# circuit.net
KiCad netlist of a schematic drawn in EAGLE
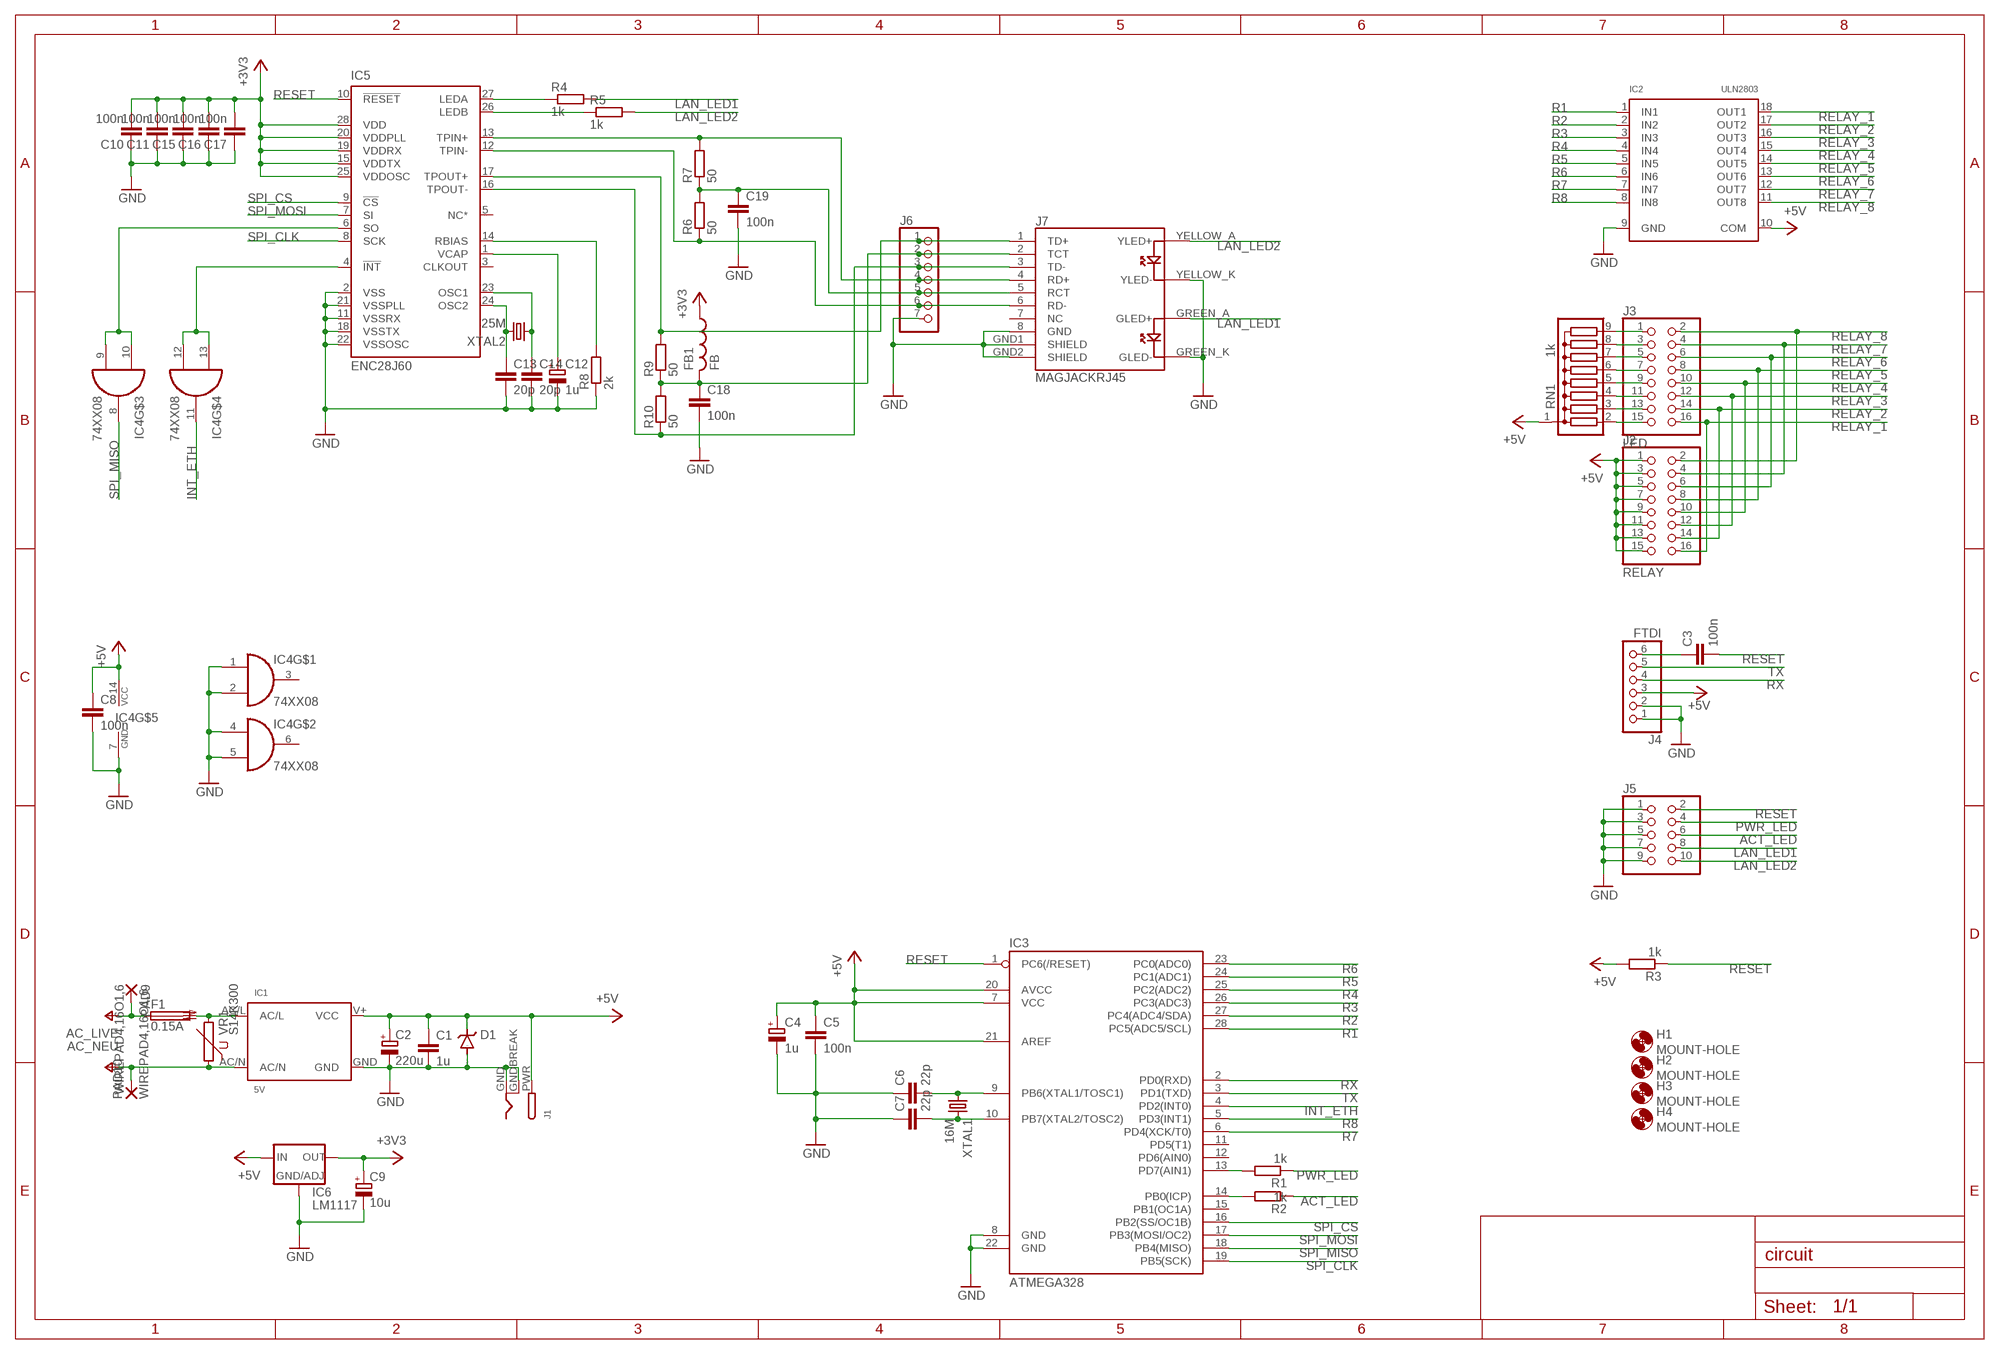
[diagram p0: schematic, sheet 1]

(export (version "E")
  (design (tool "Eeschema 10.0.6"))
  (components
    (comp (ref "C1")
      (value "1u")
      (footprint "eagle-import:C050-025X075")
      (libsource (lib "eagle-import") (part "CAPACITORC050-025X075"))
    )
    (comp (ref "C2")
      (value "220u")
      (footprint "eagle-import:E2,5-6")
      (libsource (lib "eagle-import") (part "CAPACITOR_POL2.5/6"))
    )
    (comp (ref "C3")
      (value "100n")
      (footprint "eagle-import:C050-025X075")
      (libsource (lib "eagle-import") (part "CAPACITORC050-025X075"))
    )
    (comp (ref "C4")
      (value "1u")
      (footprint "eagle-import:E5-5")
      (libsource (lib "eagle-import") (part "CAPACITOR_POL5/5"))
    )
    (comp (ref "C5")
      (value "100n")
      (footprint "eagle-import:C050-025X075")
      (libsource (lib "eagle-import") (part "CAPACITORC050-025X075"))
    )
    (comp (ref "C6")
      (value "22p")
      (footprint "eagle-import:C025-025X050")
      (libsource (lib "eagle-import") (part "CAPACITORC025-025X050"))
    )
    (comp (ref "C7")
      (value "22p")
      (footprint "eagle-import:C025-025X050")
      (libsource (lib "eagle-import") (part "CAPACITORC025-025X050"))
    )
    (comp (ref "C8")
      (value "100n")
      (footprint "eagle-import:C050-025X075")
      (libsource (lib "eagle-import") (part "CAPACITORC050-025X075"))
    )
    (comp (ref "C9")
      (value "10u")
      (footprint "eagle-import:E5-5")
      (libsource (lib "eagle-import") (part "CAPACITOR_POL5/5"))
    )
    (comp (ref "C10")
      (value "100n")
      (footprint "eagle-import:C050-025X075")
      (libsource (lib "eagle-import") (part "CAPACITORC050-025X075"))
    )
    (comp (ref "C11")
      (value "100n")
      (footprint "eagle-import:C050-025X075")
      (libsource (lib "eagle-import") (part "CAPACITORC050-025X075"))
    )
    (comp (ref "C12")
      (value "1u")
      (footprint "eagle-import:E5-5")
      (libsource (lib "eagle-import") (part "CAPACITOR_POL5/5"))
    )
    (comp (ref "C13")
      (value "20p")
      (footprint "eagle-import:C025-025X050")
      (libsource (lib "eagle-import") (part "CAPACITORC025-025X050"))
    )
    (comp (ref "C14")
      (value "20p")
      (footprint "eagle-import:C025-025X050")
      (libsource (lib "eagle-import") (part "CAPACITORC025-025X050"))
    )
    (comp (ref "C15")
      (value "100n")
      (footprint "eagle-import:C050-025X075")
      (libsource (lib "eagle-import") (part "CAPACITORC050-025X075"))
    )
    (comp (ref "C16")
      (value "100n")
      (footprint "eagle-import:C050-025X075")
      (libsource (lib "eagle-import") (part "CAPACITORC050-025X075"))
    )
    (comp (ref "C17")
      (value "100n")
      (footprint "eagle-import:C050-025X075")
      (libsource (lib "eagle-import") (part "CAPACITORC050-025X075"))
    )
    (comp (ref "C18")
      (value "100n")
      (footprint "eagle-import:C050-025X075")
      (libsource (lib "eagle-import") (part "CAPACITORC050-025X075"))
    )
    (comp (ref "C19")
      (value "100n")
      (footprint "eagle-import:C050-025X075")
      (libsource (lib "eagle-import") (part "CAPACITORC050-025X075"))
    )
    (comp (ref "D1")
      (value "DIODE-TVSDO15")
      (footprint "eagle-import:DO15")
      (libsource (lib "eagle-import") (part "DIODE-TVSDO15"))
    )
    (comp (ref "F1")
      (value "0.15A")
      (footprint "eagle-import:5X20_FUSE")
      (libsource (lib "eagle-import") (part "5X20_FUSE"))
    )
    (comp (ref "FB1") (value "FB") (footprint "eagle-import:FB") (libsource (lib "eagle-import") (part "FB")))
    (comp (ref "H1")
      (value "MOUNT-HOLE")
      (footprint "eagle-import:3,2")
      (libsource (lib "eagle-import") (part "MOUNT-HOLE"))
    )
    (comp (ref "H2")
      (value "MOUNT-HOLE")
      (footprint "eagle-import:3,2")
      (libsource (lib "eagle-import") (part "MOUNT-HOLE"))
    )
    (comp (ref "H3")
      (value "MOUNT-HOLE")
      (footprint "eagle-import:3,2")
      (libsource (lib "eagle-import") (part "MOUNT-HOLE"))
    )
    (comp (ref "H4")
      (value "MOUNT-HOLE")
      (footprint "eagle-import:3,2")
      (libsource (lib "eagle-import") (part "MOUNT-HOLE"))
    )
    (comp (ref "IC1")
      (value "5V")
      (footprint "eagle-import:LD_AMEL10")
      (libsource (lib "eagle-import") (part "AC-DC_PSUAMEL10"))
    )
    (comp (ref "IC2")
      (value "ULN2803")
      (footprint "eagle-import:DIL18")
      (libsource (lib "eagle-import") (part "ULN2803"))
    )
    (comp (ref "IC3")
      (value "ATMEGA328")
      (footprint "eagle-import:DIL28")
      (libsource (lib "eagle-import") (part "ATMEGA328"))
    )
    (comp (ref "IC4")
      (value "74XX08")
      (footprint "eagle-import:DIL14")
      (libsource (lib "eagle-import") (part "74XX08"))
    )
    (comp (ref "IC5")
      (value "ENC28J60")
      (footprint "eagle-import:DIL28")
      (libsource (lib "eagle-import") (part "ENC28J60"))
    )
    (comp (ref "IC6")
      (value "LM1117")
      (footprint "eagle-import:TO220V")
      (libsource (lib "eagle-import") (part "LM1117"))
    )
    (comp (ref "J1")
      (value "DCBARRELPTH")
      (footprint "eagle-import:DCJACK_2MM_PTH")
      (libsource (lib "eagle-import") (part "DCBARRELPTH"))
    )
    (comp (ref "J2")
      (value "RELAY")
      (footprint "eagle-import:2X08")
      (libsource (lib "eagle-import") (part "PINHD-2X8"))
    )
    (comp (ref "J3")
      (value "LED")
      (footprint "eagle-import:2X08")
      (libsource (lib "eagle-import") (part "PINHD-2X8"))
    )
    (comp (ref "J4")
      (value "FTDI")
      (footprint "eagle-import:1X06")
      (libsource (lib "eagle-import") (part "PINHD-1X6"))
    )
    (comp (ref "J5")
      (value "PINHD-2X5")
      (footprint "eagle-import:2X05")
      (libsource (lib "eagle-import") (part "PINHD-2X5"))
    )
    (comp (ref "J6")
      (value "PINHD-1X7")
      (footprint "eagle-import:1X07")
      (libsource (lib "eagle-import") (part "PINHD-1X7"))
    )
    (comp (ref "J7")
      (value "MAGJACKRJ45")
      (footprint "eagle-import:MAGJACK")
      (libsource (lib "eagle-import") (part "MAGJACKRJ45"))
    )
    (comp (ref "PAD9")
      (value "WIREPAD4,16O1,6")
      (footprint "eagle-import:4,16O1,6")
      (libsource (lib "eagle-import") (part "WIREPAD4,16O1,6"))
    )
    (comp (ref "PAD10")
      (value "WIREPAD4,16O1,6")
      (footprint "eagle-import:4,16O1,6")
      (libsource (lib "eagle-import") (part "WIREPAD4,16O1,6"))
    )
    (comp (ref "R1")
      (value "1k")
      (footprint "eagle-import:0207_10")
      (libsource (lib "eagle-import") (part "RESISTOR"))
    )
    (comp (ref "R2")
      (value "1k")
      (footprint "eagle-import:0207_10")
      (libsource (lib "eagle-import") (part "RESISTOR"))
    )
    (comp (ref "R3")
      (value "1k")
      (footprint "eagle-import:0207_10")
      (libsource (lib "eagle-import") (part "RESISTOR"))
    )
    (comp (ref "R4")
      (value "1k")
      (footprint "eagle-import:0207_10")
      (libsource (lib "eagle-import") (part "RESISTOR"))
    )
    (comp (ref "R5")
      (value "1k")
      (footprint "eagle-import:0207_10")
      (libsource (lib "eagle-import") (part "RESISTOR"))
    )
    (comp (ref "R6")
      (value "50")
      (footprint "eagle-import:0207_10")
      (libsource (lib "eagle-import") (part "RESISTOR"))
    )
    (comp (ref "R7")
      (value "50")
      (footprint "eagle-import:0207_10")
      (libsource (lib "eagle-import") (part "RESISTOR"))
    )
    (comp (ref "R8")
      (value "2k")
      (footprint "eagle-import:0207_10")
      (libsource (lib "eagle-import") (part "RESISTOR"))
    )
    (comp (ref "R9")
      (value "50")
      (footprint "eagle-import:0207_10")
      (libsource (lib "eagle-import") (part "RESISTOR"))
    )
    (comp (ref "R10")
      (value "50")
      (footprint "eagle-import:0207_10")
      (libsource (lib "eagle-import") (part "RESISTOR"))
    )
    (comp (ref "RN1")
      (value "1k")
      (footprint "eagle-import:SIL9")
      (libsource (lib "eagle-import") (part "G08R"))
    )
    (comp (ref "VR1")
      (value "S14K300")
      (footprint "eagle-import:S14K300")
      (libsource (lib "eagle-import") (part "S14K300"))
    )
    (comp (ref "XTAL1")
      (value "16M")
      (footprint "eagle-import:HC49_S")
      (libsource (lib "eagle-import") (part "CRYSTAL"))
    )
    (comp (ref "XTAL2")
      (value "25M")
      (footprint "eagle-import:HC49_S")
      (libsource (lib "eagle-import") (part "CRYSTAL"))
    )
  )
  (nets
    (net (code "1") (name "+3V3") (class "Default")
      (node (ref "C10") (pin "2") (pinfunction "2_2") (pintype "passive"))
      (node (ref "C11") (pin "2") (pinfunction "2_2") (pintype "passive"))
      (node (ref "C15") (pin "2") (pinfunction "2_2") (pintype "passive"))
      (node (ref "C16") (pin "2") (pinfunction "2_2") (pintype "passive"))
      (node (ref "C17") (pin "2") (pinfunction "2_2") (pintype "passive"))
      (node (ref "C9") (pin "+") (pinfunction "+_+") (pintype "passive"))
      (node (ref "FB1") (pin "P$1") (pinfunction "1_P$1") (pintype "passive"))
      (node (ref "IC5") (pin "15") (pinfunction "VDDTX_15") (pintype "input"))
      (node (ref "IC5") (pin "19") (pinfunction "VDDRX_19") (pintype "input"))
      (node (ref "IC5") (pin "20") (pinfunction "VDDPLL_20") (pintype "input"))
      (node (ref "IC5") (pin "25") (pinfunction "VDDOSC_25") (pintype "input"))
      (node (ref "IC5") (pin "28") (pinfunction "VDD_28") (pintype "input"))
      (node (ref "IC6") (pin "2") (pinfunction "OUT_2") (pintype "passive"))
    )
    (net (code "2") (name "+5V") (class "Default")
      (node (ref "C1") (pin "1") (pinfunction "1_1") (pintype "passive"))
      (node (ref "C2") (pin "+") (pinfunction "+_+") (pintype "passive"))
      (node (ref "C4") (pin "+") (pinfunction "+_+") (pintype "passive"))
      (node (ref "C5") (pin "1") (pinfunction "1_1") (pintype "passive"))
      (node (ref "C8") (pin "1") (pinfunction "1_1") (pintype "passive"))
      (node (ref "D1") (pin "C") (pinfunction "C_C") (pintype "passive"))
      (node (ref "IC1") (pin "V+") (pinfunction "VCC_V+") (pintype "bidirectional"))
      (node (ref "IC2") (pin "10") (pinfunction "COM_10") (pintype "bidirectional"))
      (node (ref "IC3") (pin "20") (pinfunction "AVCC_20") (pintype "bidirectional"))
      (node (ref "IC3") (pin "21") (pinfunction "AREF_21") (pintype "bidirectional"))
      (node (ref "IC3") (pin "7") (pinfunction "VCC_7") (pintype "bidirectional"))
      (node (ref "IC4") (pin "14") (pinfunction "VCC_14") (pintype "power_in"))
      (node (ref "IC6") (pin "3") (pinfunction "IN_3") (pintype "input"))
      (node (ref "J1") (pin "PWR") (pinfunction "PWR_PWR") (pintype "power_in"))
      (node (ref "J2") (pin "1") (pinfunction "1_1") (pintype "passive"))
      (node (ref "J2") (pin "11") (pinfunction "11_11") (pintype "passive"))
      (node (ref "J2") (pin "13") (pinfunction "13_13") (pintype "passive"))
      (node (ref "J2") (pin "15") (pinfunction "15_15") (pintype "passive"))
      (node (ref "J2") (pin "3") (pinfunction "3_3") (pintype "passive"))
      (node (ref "J2") (pin "5") (pinfunction "5_5") (pintype "passive"))
      (node (ref "J2") (pin "7") (pinfunction "7_7") (pintype "passive"))
      (node (ref "J2") (pin "9") (pinfunction "9_9") (pintype "passive"))
      (node (ref "J4") (pin "3") (pinfunction "3_3") (pintype "passive"))
      (node (ref "R3") (pin "2") (pinfunction "2_2") (pintype "passive"))
      (node (ref "RN1") (pin "1") (pinfunction "1_1") (pintype "passive"))
    )
    (net (code "3") (name "/ACT_LED") (class "Default")
      (node (ref "J5") (pin "6") (pinfunction "6_6") (pintype "passive"))
      (node (ref "R2") (pin "1") (pinfunction "1_1") (pintype "passive"))
    )
    (net (code "4") (name "/INT_ETH") (class "Default")
      (node (ref "IC3") (pin "4") (pinfunction "PD2(INT0)_4") (pintype "bidirectional"))
      (node (ref "IC4") (pin "11") (pinfunction "O_11") (pintype "open_collector"))
    )
    (net (code "5") (name "/LAN_LED1") (class "Default")
      (node (ref "J5") (pin "8") (pinfunction "8_8") (pintype "passive"))
      (node (ref "J7") (pin "GREEN_A") (pinfunction "GLED+_GREEN_A") (pintype "bidirectional"))
      (node (ref "R4") (pin "2") (pinfunction "2_2") (pintype "passive"))
    )
    (net (code "6") (name "/LAN_LED2") (class "Default")
      (node (ref "J5") (pin "10") (pinfunction "10_10") (pintype "passive"))
      (node (ref "J7") (pin "YELLOW_A") (pinfunction "YLED+_YELLOW_A") (pintype "bidirectional"))
      (node (ref "R5") (pin "2") (pinfunction "2_2") (pintype "passive"))
    )
    (net (code "7") (name "/PWR_LED") (class "Default")
      (node (ref "J5") (pin "4") (pinfunction "4_4") (pintype "passive"))
      (node (ref "R1") (pin "1") (pinfunction "1_1") (pintype "passive"))
    )
    (net (code "8") (name "/R1") (class "Default")
      (node (ref "IC2") (pin "1") (pinfunction "IN1_1") (pintype "bidirectional"))
      (node (ref "IC3") (pin "28") (pinfunction "PC5(ADC5/SCL)_28") (pintype "bidirectional"))
    )
    (net (code "9") (name "/R2") (class "Default")
      (node (ref "IC2") (pin "2") (pinfunction "IN2_2") (pintype "bidirectional"))
      (node (ref "IC3") (pin "27") (pinfunction "PC4(ADC4/SDA)_27") (pintype "bidirectional"))
    )
    (net (code "10") (name "/R3") (class "Default")
      (node (ref "IC2") (pin "3") (pinfunction "IN3_3") (pintype "bidirectional"))
      (node (ref "IC3") (pin "26") (pinfunction "PC3(ADC3)_26") (pintype "bidirectional"))
    )
    (net (code "11") (name "/R4") (class "Default")
      (node (ref "IC2") (pin "4") (pinfunction "IN4_4") (pintype "bidirectional"))
      (node (ref "IC3") (pin "25") (pinfunction "PC2(ADC2)_25") (pintype "bidirectional"))
    )
    (net (code "12") (name "/R5") (class "Default")
      (node (ref "IC2") (pin "5") (pinfunction "IN5_5") (pintype "bidirectional"))
      (node (ref "IC3") (pin "24") (pinfunction "PC1(ADC1)_24") (pintype "bidirectional"))
    )
    (net (code "13") (name "/R6") (class "Default")
      (node (ref "IC2") (pin "6") (pinfunction "IN6_6") (pintype "bidirectional"))
      (node (ref "IC3") (pin "23") (pinfunction "PC0(ADC0)_23") (pintype "bidirectional"))
    )
    (net (code "14") (name "/R7") (class "Default")
      (node (ref "IC2") (pin "7") (pinfunction "IN7_7") (pintype "bidirectional"))
      (node (ref "IC3") (pin "6") (pinfunction "PD4(XCK/T0)_6") (pintype "bidirectional"))
    )
    (net (code "15") (name "/R8") (class "Default")
      (node (ref "IC2") (pin "8") (pinfunction "IN8_8") (pintype "bidirectional"))
      (node (ref "IC3") (pin "5") (pinfunction "PD3(INT1)_5") (pintype "bidirectional"))
    )
    (net (code "16") (name "/RELAY_1") (class "Default")
      (node (ref "IC2") (pin "18") (pinfunction "OUT1_18") (pintype "bidirectional"))
      (node (ref "J2") (pin "16") (pinfunction "16_16") (pintype "passive"))
      (node (ref "J3") (pin "16") (pinfunction "16_16") (pintype "passive"))
    )
    (net (code "17") (name "/RELAY_2") (class "Default")
      (node (ref "IC2") (pin "17") (pinfunction "OUT2_17") (pintype "bidirectional"))
      (node (ref "J2") (pin "14") (pinfunction "14_14") (pintype "passive"))
      (node (ref "J3") (pin "14") (pinfunction "14_14") (pintype "passive"))
    )
    (net (code "18") (name "/RELAY_3") (class "Default")
      (node (ref "IC2") (pin "16") (pinfunction "OUT3_16") (pintype "bidirectional"))
      (node (ref "J2") (pin "12") (pinfunction "12_12") (pintype "passive"))
      (node (ref "J3") (pin "12") (pinfunction "12_12") (pintype "passive"))
    )
    (net (code "19") (name "/RELAY_4") (class "Default")
      (node (ref "IC2") (pin "15") (pinfunction "OUT4_15") (pintype "bidirectional"))
      (node (ref "J2") (pin "10") (pinfunction "10_10") (pintype "passive"))
      (node (ref "J3") (pin "10") (pinfunction "10_10") (pintype "passive"))
    )
    (net (code "20") (name "/RELAY_5") (class "Default")
      (node (ref "IC2") (pin "14") (pinfunction "OUT5_14") (pintype "bidirectional"))
      (node (ref "J2") (pin "8") (pinfunction "8_8") (pintype "passive"))
      (node (ref "J3") (pin "8") (pinfunction "8_8") (pintype "passive"))
    )
    (net (code "21") (name "/RELAY_6") (class "Default")
      (node (ref "IC2") (pin "13") (pinfunction "OUT6_13") (pintype "bidirectional"))
      (node (ref "J2") (pin "6") (pinfunction "6_6") (pintype "passive"))
      (node (ref "J3") (pin "6") (pinfunction "6_6") (pintype "passive"))
    )
    (net (code "22") (name "/RELAY_7") (class "Default")
      (node (ref "IC2") (pin "12") (pinfunction "OUT7_12") (pintype "bidirectional"))
      (node (ref "J2") (pin "4") (pinfunction "4_4") (pintype "passive"))
      (node (ref "J3") (pin "4") (pinfunction "4_4") (pintype "passive"))
    )
    (net (code "23") (name "/RELAY_8") (class "Default")
      (node (ref "IC2") (pin "11") (pinfunction "OUT8_11") (pintype "bidirectional"))
      (node (ref "J2") (pin "2") (pinfunction "2_2") (pintype "passive"))
      (node (ref "J3") (pin "2") (pinfunction "2_2") (pintype "passive"))
    )
    (net (code "24") (name "/RESET") (class "Default")
      (node (ref "C3") (pin "2") (pinfunction "2_2") (pintype "passive"))
      (node (ref "IC3") (pin "1") (pinfunction "PC6(/RESET)_1") (pintype "bidirectional"))
      (node (ref "IC5") (pin "10") (pinfunction "~{RESET}_10") (pintype "input"))
      (node (ref "J5") (pin "2") (pinfunction "2_2") (pintype "passive"))
      (node (ref "R3") (pin "1") (pinfunction "1_1") (pintype "passive"))
    )
    (net (code "25") (name "/RX") (class "Default")
      (node (ref "IC3") (pin "2") (pinfunction "PD0(RXD)_2") (pintype "bidirectional"))
      (node (ref "J4") (pin "4") (pinfunction "4_4") (pintype "passive"))
    )
    (net (code "26") (name "/SPI_CLK") (class "Default")
      (node (ref "IC3") (pin "19") (pinfunction "PB5(SCK)_19") (pintype "bidirectional"))
      (node (ref "IC5") (pin "8") (pinfunction "SCK_8") (pintype "input"))
    )
    (net (code "27") (name "/SPI_CS") (class "Default")
      (node (ref "IC3") (pin "16") (pinfunction "PB2(SS/OC1B)_16") (pintype "bidirectional"))
      (node (ref "IC5") (pin "9") (pinfunction "~{CS}_9") (pintype "input"))
    )
    (net (code "28") (name "/SPI_MISO") (class "Default")
      (node (ref "IC3") (pin "18") (pinfunction "PB4(MISO)_18") (pintype "bidirectional"))
      (node (ref "IC4") (pin "8") (pinfunction "O_8") (pintype "open_collector"))
    )
    (net (code "29") (name "/SPI_MOSI") (class "Default")
      (node (ref "IC3") (pin "17") (pinfunction "PB3(MOSI/OC2)_17") (pintype "bidirectional"))
      (node (ref "IC5") (pin "7") (pinfunction "SI_7") (pintype "input"))
    )
    (net (code "30") (name "/TX") (class "Default")
      (node (ref "IC3") (pin "3") (pinfunction "PD1(TXD)_3") (pintype "bidirectional"))
      (node (ref "J4") (pin "5") (pinfunction "5_5") (pintype "passive"))
    )
    (net (code "31") (name "AC_LIVE") (class "Default")
      (node (ref "F1") (pin "1A") (pinfunction "1_1A") (pintype "passive"))
      (node (ref "F1") (pin "1B") (pinfunction "1_1B") (pintype "passive"))
      (node (ref "PAD9") (pin "1") (pinfunction "P_1") (pintype "passive"))
    )
    (net (code "32") (name "AC_NEU") (class "Default")
      (node (ref "IC1") (pin "AC/N") (pinfunction "AC/N_AC/N") (pintype "bidirectional"))
      (node (ref "PAD10") (pin "1") (pinfunction "P_1") (pintype "passive"))
      (node (ref "VR1") (pin "1") (pinfunction "1_1") (pintype "passive"))
    )
    (net (code "33") (name "GND") (class "Default")
      (node (ref "C1") (pin "2") (pinfunction "2_2") (pintype "passive"))
      (node (ref "C10") (pin "1") (pinfunction "1_1") (pintype "passive"))
      (node (ref "C11") (pin "1") (pinfunction "1_1") (pintype "passive"))
      (node (ref "C12") (pin "-") (pinfunction "-_-") (pintype "passive"))
      (node (ref "C13") (pin "2") (pinfunction "2_2") (pintype "passive"))
      (node (ref "C14") (pin "2") (pinfunction "2_2") (pintype "passive"))
      (node (ref "C15") (pin "1") (pinfunction "1_1") (pintype "passive"))
      (node (ref "C16") (pin "1") (pinfunction "1_1") (pintype "passive"))
      (node (ref "C17") (pin "1") (pinfunction "1_1") (pintype "passive"))
      (node (ref "C18") (pin "2") (pinfunction "2_2") (pintype "passive"))
      (node (ref "C19") (pin "2") (pinfunction "2_2") (pintype "passive"))
      (node (ref "C2") (pin "-") (pinfunction "-_-") (pintype "passive"))
      (node (ref "C4") (pin "-") (pinfunction "-_-") (pintype "passive"))
      (node (ref "C5") (pin "2") (pinfunction "2_2") (pintype "passive"))
      (node (ref "C6") (pin "1") (pinfunction "1_1") (pintype "passive"))
      (node (ref "C7") (pin "1") (pinfunction "1_1") (pintype "passive"))
      (node (ref "C8") (pin "2") (pinfunction "2_2") (pintype "passive"))
      (node (ref "C9") (pin "-") (pinfunction "-_-") (pintype "passive"))
      (node (ref "D1") (pin "A") (pinfunction "A_A") (pintype "passive"))
      (node (ref "IC1") (pin "GND") (pinfunction "GND_GND") (pintype "bidirectional"))
      (node (ref "IC2") (pin "9") (pinfunction "GND_9") (pintype "bidirectional"))
      (node (ref "IC3") (pin "22") (pinfunction "GND_22") (pintype "bidirectional"))
      (node (ref "IC3") (pin "8") (pinfunction "GND_8") (pintype "bidirectional"))
      (node (ref "IC4") (pin "1") (pinfunction "I0_1") (pintype "input"))
      (node (ref "IC4") (pin "2") (pinfunction "I1_2") (pintype "input"))
      (node (ref "IC4") (pin "4") (pinfunction "I0_4") (pintype "input"))
      (node (ref "IC4") (pin "5") (pinfunction "I1_5") (pintype "input"))
      (node (ref "IC4") (pin "7") (pinfunction "GND_7") (pintype "power_in"))
      (node (ref "IC5") (pin "11") (pinfunction "VSSRX_11") (pintype "input"))
      (node (ref "IC5") (pin "18") (pinfunction "VSSTX_18") (pintype "input"))
      (node (ref "IC5") (pin "2") (pinfunction "VSS_2") (pintype "input"))
      (node (ref "IC5") (pin "21") (pinfunction "VSSPLL_21") (pintype "input"))
      (node (ref "IC5") (pin "22") (pinfunction "VSSOSC_22") (pintype "input"))
      (node (ref "IC6") (pin "1") (pinfunction "GND/ADJ_1") (pintype "input"))
      (node (ref "J1") (pin "GND") (pinfunction "GND_GND") (pintype "power_in"))
      (node (ref "J1") (pin "GNDBREAK") (pinfunction "GNDBREAK_GNDBREAK") (pintype "power_in"))
      (node (ref "J4") (pin "1") (pinfunction "1_1") (pintype "passive"))
      (node (ref "J4") (pin "2") (pinfunction "2_2") (pintype "passive"))
      (node (ref "J5") (pin "1") (pinfunction "1_1") (pintype "passive"))
      (node (ref "J5") (pin "3") (pinfunction "3_3") (pintype "passive"))
      (node (ref "J5") (pin "5") (pinfunction "5_5") (pintype "passive"))
      (node (ref "J5") (pin "7") (pinfunction "7_7") (pintype "passive"))
      (node (ref "J5") (pin "9") (pinfunction "9_9") (pintype "passive"))
      (node (ref "J6") (pin "7") (pinfunction "7_7") (pintype "passive"))
      (node (ref "J7") (pin "8") (pinfunction "GND_8") (pintype "bidirectional"))
      (node (ref "J7") (pin "GND1") (pinfunction "SHIELD_GND1") (pintype "bidirectional"))
      (node (ref "J7") (pin "GND2") (pinfunction "SHIELD_GND2") (pintype "bidirectional"))
      (node (ref "J7") (pin "GREEN_K") (pinfunction "GLED-_GREEN_K") (pintype "bidirectional"))
      (node (ref "J7") (pin "YELLOW_K") (pinfunction "YLED-_YELLOW_K") (pintype "bidirectional"))
      (node (ref "R8") (pin "1") (pinfunction "1_1") (pintype "passive"))
    )
    (net (code "34") (name "Net-(C3-Pad1)") (class "Default")
      (node (ref "C3") (pin "1") (pinfunction "1_1") (pintype "passive"))
      (node (ref "J4") (pin "6") (pinfunction "6_6") (pintype "passive"))
    )
    (net (code "35") (name "Net-(F1-2-Pad2A)") (class "Default")
      (node (ref "F1") (pin "2A") (pinfunction "2_2A") (pintype "passive"))
      (node (ref "F1") (pin "2B") (pinfunction "2_2B") (pintype "passive"))
      (node (ref "IC1") (pin "AC/L") (pinfunction "AC/L_AC/L") (pintype "bidirectional"))
      (node (ref "VR1") (pin "2") (pinfunction "2_2") (pintype "passive"))
    )
    (net (code "36") (name "Net-(FB1-2)") (class "Default")
      (node (ref "C18") (pin "1") (pinfunction "1_1") (pintype "passive"))
      (node (ref "FB1") (pin "P$2") (pinfunction "2_P$2") (pintype "passive"))
      (node (ref "J6") (pin "2") (pinfunction "2_2") (pintype "passive"))
      (node (ref "J7") (pin "2") (pinfunction "TCT_2") (pintype "bidirectional"))
      (node (ref "R10") (pin "2") (pinfunction "2_2") (pintype "passive"))
      (node (ref "R9") (pin "1") (pinfunction "1_1") (pintype "passive"))
    )
    (net (code "37") (name "Net-(IC3-PB0(ICP))") (class "Default")
      (node (ref "IC3") (pin "14") (pinfunction "PB0(ICP)_14") (pintype "bidirectional"))
      (node (ref "R2") (pin "2") (pinfunction "2_2") (pintype "passive"))
    )
    (net (code "38") (name "Net-(IC3-PB6(XTAL1{slash}TOSC1))") (class "Default")
      (node (ref "C6") (pin "2") (pinfunction "2_2") (pintype "passive"))
      (node (ref "IC3") (pin "9") (pinfunction "PB6(XTAL1/TOSC1)_9") (pintype "bidirectional"))
      (node (ref "XTAL1") (pin "1") (pinfunction "1_1") (pintype "passive"))
    )
    (net (code "39") (name "Net-(IC3-PB7(XTAL2{slash}TOSC2))") (class "Default")
      (node (ref "C7") (pin "2") (pinfunction "2_2") (pintype "passive"))
      (node (ref "IC3") (pin "10") (pinfunction "PB7(XTAL2/TOSC2)_10") (pintype "bidirectional"))
      (node (ref "XTAL1") (pin "2") (pinfunction "2_2") (pintype "passive"))
    )
    (net (code "40") (name "Net-(IC3-PD7(AIN1))") (class "Default")
      (node (ref "IC3") (pin "13") (pinfunction "PD7(AIN1)_13") (pintype "bidirectional"))
      (node (ref "R1") (pin "2") (pinfunction "2_2") (pintype "passive"))
    )
    (net (code "41") (name "Net-(IC4C-I0)") (class "Default")
      (node (ref "IC4") (pin "10") (pinfunction "I0_10") (pintype "input"))
      (node (ref "IC4") (pin "9") (pinfunction "I1_9") (pintype "input"))
      (node (ref "IC5") (pin "6") (pinfunction "SO_6") (pintype "output"))
    )
    (net (code "42") (name "Net-(IC4D-I0)") (class "Default")
      (node (ref "IC4") (pin "12") (pinfunction "I1_12") (pintype "input"))
      (node (ref "IC4") (pin "13") (pinfunction "I0_13") (pintype "input"))
      (node (ref "IC5") (pin "4") (pinfunction "~{INT}_4") (pintype "output"))
    )
    (net (code "43") (name "Net-(IC5-LEDA)") (class "Default")
      (node (ref "IC5") (pin "27") (pinfunction "LEDA_27") (pintype "output"))
      (node (ref "R4") (pin "1") (pinfunction "1_1") (pintype "passive"))
    )
    (net (code "44") (name "Net-(IC5-LEDB)") (class "Default")
      (node (ref "IC5") (pin "26") (pinfunction "LEDB_26") (pintype "output"))
      (node (ref "R5") (pin "1") (pinfunction "1_1") (pintype "passive"))
    )
    (net (code "45") (name "Net-(IC5-OSC1)") (class "Default")
      (node (ref "C14") (pin "1") (pinfunction "1_1") (pintype "passive"))
      (node (ref "IC5") (pin "23") (pinfunction "OSC1_23") (pintype "input"))
      (node (ref "XTAL2") (pin "1") (pinfunction "1_1") (pintype "passive"))
    )
    (net (code "46") (name "Net-(IC5-OSC2)") (class "Default")
      (node (ref "C13") (pin "1") (pinfunction "1_1") (pintype "passive"))
      (node (ref "IC5") (pin "24") (pinfunction "OSC2_24") (pintype "output"))
      (node (ref "XTAL2") (pin "2") (pinfunction "2_2") (pintype "passive"))
    )
    (net (code "47") (name "Net-(IC5-RBIAS)") (class "Default")
      (node (ref "IC5") (pin "14") (pinfunction "RBIAS_14") (pintype "input"))
      (node (ref "R8") (pin "2") (pinfunction "2_2") (pintype "passive"))
    )
    (net (code "48") (name "Net-(IC5-TPIN+)") (class "Default")
      (node (ref "IC5") (pin "13") (pinfunction "TPIN+_13") (pintype "input"))
      (node (ref "J6") (pin "4") (pinfunction "4_4") (pintype "passive"))
      (node (ref "J7") (pin "4") (pinfunction "RD+_4") (pintype "bidirectional"))
      (node (ref "R7") (pin "2") (pinfunction "2_2") (pintype "passive"))
    )
    (net (code "49") (name "Net-(IC5-TPIN-)") (class "Default")
      (node (ref "IC5") (pin "12") (pinfunction "TPIN-_12") (pintype "input"))
      (node (ref "J6") (pin "6") (pinfunction "6_6") (pintype "passive"))
      (node (ref "J7") (pin "6") (pinfunction "RD-_6") (pintype "bidirectional"))
      (node (ref "R6") (pin "1") (pinfunction "1_1") (pintype "passive"))
    )
    (net (code "50") (name "Net-(IC5-TPOUT+)") (class "Default")
      (node (ref "IC5") (pin "17") (pinfunction "TPOUT+_17") (pintype "output"))
      (node (ref "J6") (pin "1") (pinfunction "1_1") (pintype "passive"))
      (node (ref "J7") (pin "1") (pinfunction "TD+_1") (pintype "bidirectional"))
      (node (ref "R9") (pin "2") (pinfunction "2_2") (pintype "passive"))
    )
    (net (code "51") (name "Net-(IC5-TPOUT-)") (class "Default")
      (node (ref "IC5") (pin "16") (pinfunction "TPOUT-_16") (pintype "output"))
      (node (ref "J6") (pin "3") (pinfunction "3_3") (pintype "passive"))
      (node (ref "J7") (pin "3") (pinfunction "TD-_3") (pintype "bidirectional"))
      (node (ref "R10") (pin "1") (pinfunction "1_1") (pintype "passive"))
    )
    (net (code "52") (name "Net-(IC5-VCAP)") (class "Default")
      (node (ref "C12") (pin "+") (pinfunction "+_+") (pintype "passive"))
      (node (ref "IC5") (pin "1") (pinfunction "VCAP_1") (pintype "input"))
    )
    (net (code "53") (name "Net-(J3-Pad1)") (class "Default")
      (node (ref "J3") (pin "1") (pinfunction "1_1") (pintype "passive"))
      (node (ref "RN1") (pin "9") (pinfunction "9_9") (pintype "passive"))
    )
    (net (code "54") (name "Net-(J3-Pad3)") (class "Default")
      (node (ref "J3") (pin "3") (pinfunction "3_3") (pintype "passive"))
      (node (ref "RN1") (pin "8") (pinfunction "8_8") (pintype "passive"))
    )
    (net (code "55") (name "Net-(J3-Pad5)") (class "Default")
      (node (ref "J3") (pin "5") (pinfunction "5_5") (pintype "passive"))
      (node (ref "RN1") (pin "7") (pinfunction "7_7") (pintype "passive"))
    )
    (net (code "56") (name "Net-(J3-Pad7)") (class "Default")
      (node (ref "J3") (pin "7") (pinfunction "7_7") (pintype "passive"))
      (node (ref "RN1") (pin "6") (pinfunction "6_6") (pintype "passive"))
    )
    (net (code "57") (name "Net-(J3-Pad9)") (class "Default")
      (node (ref "J3") (pin "9") (pinfunction "9_9") (pintype "passive"))
      (node (ref "RN1") (pin "5") (pinfunction "5_5") (pintype "passive"))
    )
    (net (code "58") (name "Net-(J3-Pad11)") (class "Default")
      (node (ref "J3") (pin "11") (pinfunction "11_11") (pintype "passive"))
      (node (ref "RN1") (pin "4") (pinfunction "4_4") (pintype "passive"))
    )
    (net (code "59") (name "Net-(J3-Pad13)") (class "Default")
      (node (ref "J3") (pin "13") (pinfunction "13_13") (pintype "passive"))
      (node (ref "RN1") (pin "3") (pinfunction "3_3") (pintype "passive"))
    )
    (net (code "60") (name "Net-(J3-Pad15)") (class "Default")
      (node (ref "J3") (pin "15") (pinfunction "15_15") (pintype "passive"))
      (node (ref "RN1") (pin "2") (pinfunction "2_2") (pintype "passive"))
    )
    (net (code "61") (name "Net-(J7-RCT)") (class "Default")
      (node (ref "C19") (pin "1") (pinfunction "1_1") (pintype "passive"))
      (node (ref "J6") (pin "5") (pinfunction "5_5") (pintype "passive"))
      (node (ref "J7") (pin "5") (pinfunction "RCT_5") (pintype "bidirectional"))
      (node (ref "R6") (pin "2") (pinfunction "2_2") (pintype "passive"))
      (node (ref "R7") (pin "1") (pinfunction "1_1") (pintype "passive"))
    )
    (net (code "62") (name "unconnected-(IC3-PB1(OC1A)-Pad15)") (class "Default")
      (node (ref "IC3") (pin "15") (pinfunction "PB1(OC1A)_15") (pintype "bidirectional"))
    )
    (net (code "63") (name "unconnected-(IC3-PD5(T1)-Pad11)") (class "Default")
      (node (ref "IC3") (pin "11") (pinfunction "PD5(T1)_11") (pintype "bidirectional"))
    )
    (net (code "64") (name "unconnected-(IC3-PD6(AIN0)-Pad12)") (class "Default")
      (node (ref "IC3") (pin "12") (pinfunction "PD6(AIN0)_12") (pintype "bidirectional"))
    )
    (net (code "65") (name "unconnected-(IC4A-O-Pad3)") (class "Default")
      (node (ref "IC4") (pin "3") (pinfunction "O_3") (pintype "open_collector"))
    )
    (net (code "66") (name "unconnected-(IC4B-O-Pad6)") (class "Default")
      (node (ref "IC4") (pin "6") (pinfunction "O_6") (pintype "open_collector"))
    )
    (net (code "67") (name "unconnected-(IC5-CLKOUT-Pad3)") (class "Default")
      (node (ref "IC5") (pin "3") (pinfunction "CLKOUT_3") (pintype "output"))
    )
    (net (code "68") (name "unconnected-(IC5-NC*-Pad5)") (class "Default")
      (node (ref "IC5") (pin "5") (pinfunction "NC*_5") (pintype "output"))
    )
    (net (code "69") (name "unconnected-(J7-NC-Pad7)") (class "Default")
      (node (ref "J7") (pin "7") (pinfunction "NC_7") (pintype "bidirectional"))
    )
  )
)
